# Audio_interface.net
KiCad netlist of a schematic drawn in EAGLE
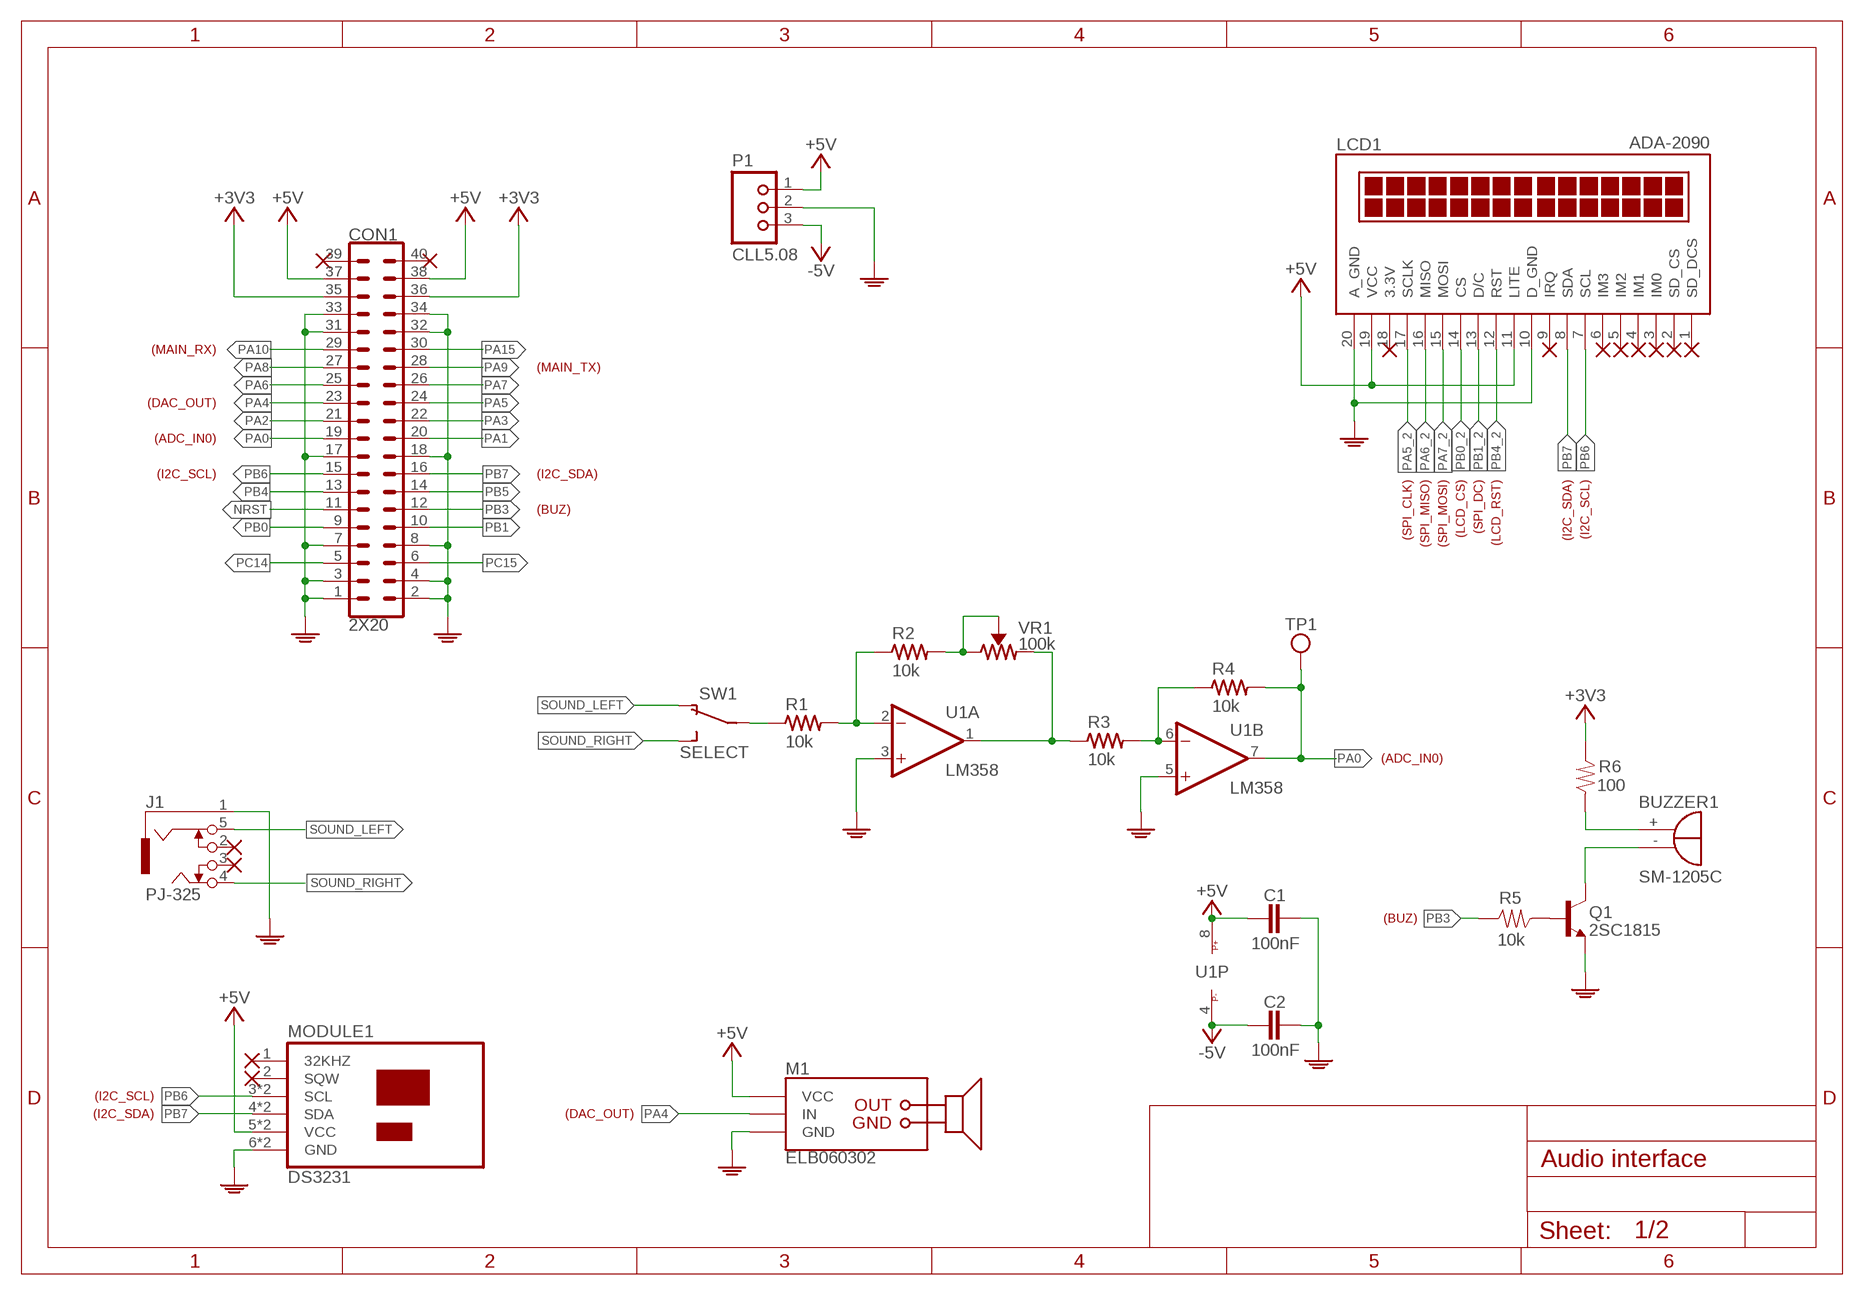
[diagram p0: schematic, sheet 1]
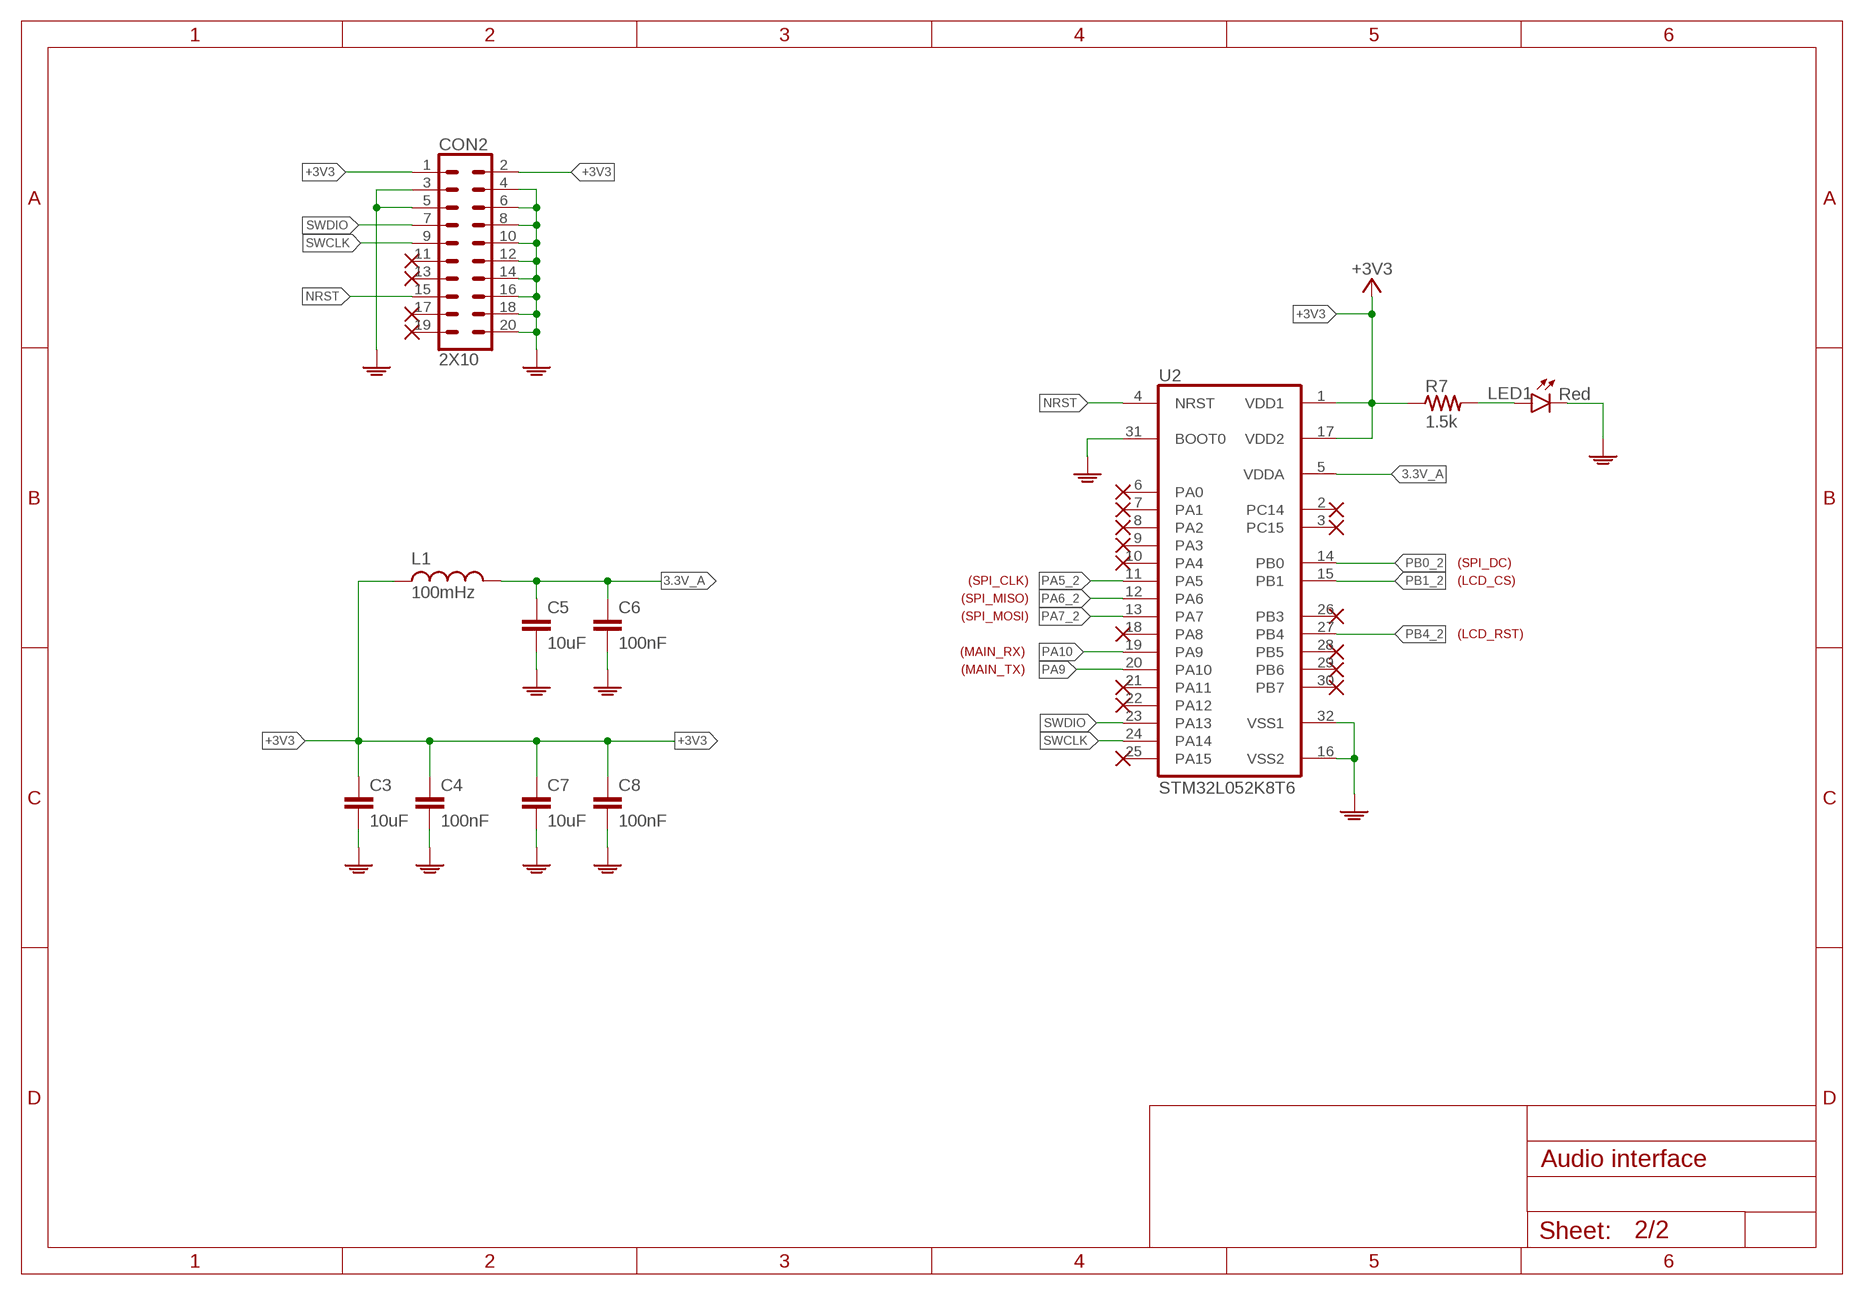
[diagram p1: schematic, sheet 2]

(export (version "E")
  (design (tool "Eeschema 10.0.6"))
  (components
    (comp (ref "C3")
      (value "10uF")
      (footprint "eagle-import:C0603K")
      (libsource (lib "eagle-import") (part "C-EUC0603K"))
    )
    (comp (ref "C4")
      (value "100nF")
      (footprint "eagle-import:C2012")
      (libsource (lib "eagle-import") (part "C-EUC2012"))
    )
    (comp (ref "C5")
      (value "10uF")
      (footprint "eagle-import:C0603K")
      (libsource (lib "eagle-import") (part "C-EUC0603K"))
    )
    (comp (ref "C6")
      (value "100nF")
      (footprint "eagle-import:C2012")
      (libsource (lib "eagle-import") (part "C-EUC2012"))
    )
    (comp (ref "C7")
      (value "10uF")
      (footprint "eagle-import:C0603K")
      (libsource (lib "eagle-import") (part "C-EUC0603K"))
    )
    (comp (ref "C8")
      (value "100nF")
      (footprint "eagle-import:C2012")
      (libsource (lib "eagle-import") (part "C-EUC2012"))
    )
    (comp (ref "CON2")
      (value "2X10")
      (footprint "eagle-import:2X10(MALE)")
      (libsource (lib "eagle-import") (part "HEADER_2X10_(PIN)"))
    )
    (comp (ref "L1")
      (value "100mHz")
      (footprint "eagle-import:C0603K")
      (libsource (lib "eagle-import") (part "L-US"))
    )
    (comp (ref "LED1")
      (value "Red")
      (footprint "eagle-import:CHIP_0805(LED)")
      (libsource (lib "eagle-import") (part "LED(1-COLOR)_(0805)"))
    )
    (comp (ref "R7")
      (value "1.5k")
      (footprint "eagle-import:2012")
      (libsource (lib "eagle-import") (part "RES_(2012)"))
    )
    (comp (ref "U2")
      (value "STM32L052K8T6")
      (footprint "eagle-import:LQFP32")
      (libsource (lib "eagle-import") (part "STM32L052K6T6"))
    )
    (comp (ref "BUZZER1")
      (value "SM-1205C")
      (footprint "eagle-import:SM-1205C")
      (libsource (lib "eagle-import") (part "BUZZER_(SM-1205C)"))
    )
    (comp (ref "C1")
      (value "100nF")
      (footprint "eagle-import:C2012")
      (libsource (lib "eagle-import") (part "C-EUC2012"))
    )
    (comp (ref "C2")
      (value "100nF")
      (footprint "eagle-import:C2012")
      (libsource (lib "eagle-import") (part "C-EUC2012"))
    )
    (comp (ref "CON1")
      (value "2X20")
      (footprint "eagle-import:2X20_VER3DEFORMATION")
      (libsource (lib "eagle-import") (part "HEADER_2X20_(VER_3DEFORMATION)"))
    )
    (comp (ref "J1")
      (value "PJ-325")
      (footprint "eagle-import:PJ-325")
      (libsource (lib "eagle-import") (part "JACK(STEREO)_(PJ-325)"))
    )
    (comp (ref "LCD1")
      (value "ADA-2090")
      (footprint "eagle-import:TOUCH_SCREEN")
      (libsource (lib "eagle-import") (part "MODULE(ADA-1770)"))
    )
    (comp (ref "M1")
      (value "ELB060302")
      (footprint "eagle-import:MODULE(ELB060302)")
      (libsource (lib "eagle-import") (part "MODULE(ELB060302)"))
    )
    (comp (ref "MODULE1")
      (value "DS3231")
      (footprint "eagle-import:MODULE(DS3231)")
      (libsource (lib "eagle-import") (part "MODULE(DS3231)"))
    )
    (comp (ref "P1")
      (value "CLL5.08")
      (footprint "eagle-import:TERMINAL(CLL5.08-03P)")
      (libsource (lib "eagle-import") (part "TERMINAL(3P)_(CLL5.08)"))
    )
    (comp (ref "Q1")
      (value "2SC1815")
      (footprint "eagle-import:SOT23")
      (libsource (lib "eagle-import") (part "TR_BJT(NPN)_(SOT23)"))
    )
    (comp (ref "R1")
      (value "10k")
      (footprint "eagle-import:2012")
      (libsource (lib "eagle-import") (part "RES_(2012)"))
    )
    (comp (ref "R2")
      (value "10k")
      (footprint "eagle-import:2012")
      (libsource (lib "eagle-import") (part "RES_(2012)"))
    )
    (comp (ref "R3")
      (value "10k")
      (footprint "eagle-import:2012")
      (libsource (lib "eagle-import") (part "RES_(2012)"))
    )
    (comp (ref "R4")
      (value "10k")
      (footprint "eagle-import:2012")
      (libsource (lib "eagle-import") (part "RES_(2012)"))
    )
    (comp (ref "R5")
      (value "10k")
      (footprint "eagle-import:2012")
      (libsource (lib "eagle-import") (part "RESSMD"))
    )
    (comp (ref "R6")
      (value "100")
      (footprint "eagle-import:2012")
      (libsource (lib "eagle-import") (part "RESSMD"))
    )
    (comp (ref "SW1")
      (value "SELECT")
      (footprint "eagle-import:SW(MSL-1C2P)")
      (libsource (lib "eagle-import") (part "SW(SPDT)_(MSL-1C2P)"))
    )
    (comp (ref "TP1")
      (value "TP_(LC-2-G)")
      (footprint "eagle-import:TP(LC-2-G)")
      (libsource (lib "eagle-import") (part "TP_(LC-2-G)"))
    )
    (comp (ref "U1")
      (value "LM358")
      (footprint "eagle-import:SO8(150MIL)")
      (libsource (lib "eagle-import") (part "LM358_(SO)"))
    )
    (comp (ref "VR1")
      (value "100k")
      (footprint "eagle-import:RTRIM(VZ067TL7)")
      (libsource (lib "eagle-import") (part "RES(VARIABLE)_(VZ067TL7)"))
    )
  )
  (nets
    (net (code "1") (name "+3V3") (class "Default")
      (node (ref "C3") (pin "1") (pinfunction "1_1") (pintype "passive"))
      (node (ref "C4") (pin "1") (pinfunction "1_1") (pintype "passive"))
      (node (ref "C7") (pin "1") (pinfunction "1_1") (pintype "passive"))
      (node (ref "C8") (pin "1") (pinfunction "1_1") (pintype "passive"))
      (node (ref "CON1") (pin "35") (pinfunction "35_35") (pintype "passive"))
      (node (ref "CON1") (pin "36") (pinfunction "36_36") (pintype "passive"))
      (node (ref "CON2") (pin "1") (pinfunction "1_1") (pintype "passive"))
      (node (ref "CON2") (pin "2") (pinfunction "2_2") (pintype "passive"))
      (node (ref "L1") (pin "1") (pinfunction "1_1") (pintype "passive"))
      (node (ref "R6") (pin "2") (pinfunction "2_2") (pintype "bidirectional"))
      (node (ref "R7") (pin "1") (pinfunction "1_1") (pintype "passive"))
      (node (ref "U2") (pin "1") (pinfunction "VDD1_1") (pintype "power_in"))
      (node (ref "U2") (pin "17") (pinfunction "VDD2_17") (pintype "power_in"))
    )
    (net (code "2") (name "+5V") (class "Default")
      (node (ref "C1") (pin "1") (pinfunction "1_1") (pintype "passive"))
      (node (ref "CON1") (pin "37") (pinfunction "37_37") (pintype "passive"))
      (node (ref "CON1") (pin "38") (pinfunction "38_38") (pintype "passive"))
      (node (ref "LCD1") (pin "11") (pinfunction "LITE_11") (pintype "bidirectional"))
      (node (ref "LCD1") (pin "19") (pinfunction "VCC_19") (pintype "bidirectional"))
      (node (ref "M1") (pin "2") (pinfunction "VCC_2") (pintype "bidirectional"))
      (node (ref "MODULE1") (pin "5") (pinfunction "VCC_5") (pintype "power_in"))
      (node (ref "MODULE1") (pin "9") (pinfunction "VCC_9") (pintype "power_in"))
      (node (ref "P1") (pin "1") (pinfunction "1_1") (pintype "passive"))
      (node (ref "U1") (pin "8") (pinfunction "P+_8") (pintype "power_in"))
    )
    (net (code "3") (name "-5V") (class "Default")
      (node (ref "C2") (pin "1") (pinfunction "1_1") (pintype "passive"))
      (node (ref "P1") (pin "3") (pinfunction "3_3") (pintype "passive"))
      (node (ref "U1") (pin "4") (pinfunction "P-_4") (pintype "power_in"))
    )
    (net (code "4") (name "3.3V_A") (class "Default")
      (node (ref "C5") (pin "1") (pinfunction "1_1") (pintype "passive"))
      (node (ref "C6") (pin "1") (pinfunction "1_1") (pintype "passive"))
      (node (ref "L1") (pin "2") (pinfunction "2_2") (pintype "passive"))
      (node (ref "U2") (pin "5") (pinfunction "VDDA_5") (pintype "power_in"))
    )
    (net (code "5") (name "GND") (class "Default")
      (node (ref "C1") (pin "2") (pinfunction "2_2") (pintype "passive"))
      (node (ref "C2") (pin "2") (pinfunction "2_2") (pintype "passive"))
      (node (ref "C3") (pin "2") (pinfunction "2_2") (pintype "passive"))
      (node (ref "C4") (pin "2") (pinfunction "2_2") (pintype "passive"))
      (node (ref "C5") (pin "2") (pinfunction "2_2") (pintype "passive"))
      (node (ref "C6") (pin "2") (pinfunction "2_2") (pintype "passive"))
      (node (ref "C7") (pin "2") (pinfunction "2_2") (pintype "passive"))
      (node (ref "C8") (pin "2") (pinfunction "2_2") (pintype "passive"))
      (node (ref "CON1") (pin "1") (pinfunction "1_1") (pintype "passive"))
      (node (ref "CON1") (pin "17") (pinfunction "17_17") (pintype "passive"))
      (node (ref "CON1") (pin "18") (pinfunction "18_18") (pintype "passive"))
      (node (ref "CON1") (pin "2") (pinfunction "2_2") (pintype "passive"))
      (node (ref "CON1") (pin "3") (pinfunction "3_3") (pintype "passive"))
      (node (ref "CON1") (pin "31") (pinfunction "31_31") (pintype "passive"))
      (node (ref "CON1") (pin "32") (pinfunction "32_32") (pintype "passive"))
      (node (ref "CON1") (pin "33") (pinfunction "33_33") (pintype "passive"))
      (node (ref "CON1") (pin "34") (pinfunction "34_34") (pintype "passive"))
      (node (ref "CON1") (pin "4") (pinfunction "4_4") (pintype "passive"))
      (node (ref "CON1") (pin "7") (pinfunction "7_7") (pintype "passive"))
      (node (ref "CON1") (pin "8") (pinfunction "8_8") (pintype "passive"))
      (node (ref "CON2") (pin "10") (pinfunction "10_10") (pintype "passive"))
      (node (ref "CON2") (pin "12") (pinfunction "12_12") (pintype "passive"))
      (node (ref "CON2") (pin "14") (pinfunction "14_14") (pintype "passive"))
      (node (ref "CON2") (pin "16") (pinfunction "16_16") (pintype "passive"))
      (node (ref "CON2") (pin "18") (pinfunction "18_18") (pintype "passive"))
      (node (ref "CON2") (pin "20") (pinfunction "20_20") (pintype "passive"))
      (node (ref "CON2") (pin "3") (pinfunction "3_3") (pintype "passive"))
      (node (ref "CON2") (pin "4") (pinfunction "4_4") (pintype "passive"))
      (node (ref "CON2") (pin "5") (pinfunction "5_5") (pintype "passive"))
      (node (ref "CON2") (pin "6") (pinfunction "6_6") (pintype "passive"))
      (node (ref "CON2") (pin "8") (pinfunction "8_8") (pintype "passive"))
      (node (ref "J1") (pin "1") (pinfunction "GND_1") (pintype "passive"))
      (node (ref "LCD1") (pin "10") (pinfunction "D_GND_10") (pintype "bidirectional"))
      (node (ref "LCD1") (pin "20") (pinfunction "A_GND_20") (pintype "bidirectional"))
      (node (ref "LED1") (pin "1") (pinfunction "C_1") (pintype "passive"))
      (node (ref "M1") (pin "3") (pinfunction "GND_3") (pintype "bidirectional"))
      (node (ref "MODULE1") (pin "10") (pinfunction "GND_10") (pintype "power_in"))
      (node (ref "MODULE1") (pin "6") (pinfunction "GND_6") (pintype "power_in"))
      (node (ref "P1") (pin "2") (pinfunction "2_2") (pintype "passive"))
      (node (ref "Q1") (pin "2") (pinfunction "E_2") (pintype "passive"))
      (node (ref "U1") (pin "3") (pinfunction "+IN_3") (pintype "input"))
      (node (ref "U1") (pin "5") (pinfunction "+IN_5") (pintype "input"))
      (node (ref "U2") (pin "16") (pinfunction "VSS2_16") (pintype "power_in"))
      (node (ref "U2") (pin "31") (pinfunction "BOOT0_31") (pintype "input"))
      (node (ref "U2") (pin "32") (pinfunction "VSS1_32") (pintype "power_in"))
    )
    (net (code "6") (name "NRST") (class "Default")
      (node (ref "CON1") (pin "11") (pinfunction "11_11") (pintype "passive"))
      (node (ref "CON2") (pin "15") (pinfunction "15_15") (pintype "passive"))
      (node (ref "U2") (pin "4") (pinfunction "NRST_4") (pintype "input"))
    )
    (net (code "7") (name "Net-(BUZZER1-Pad+)") (class "Default")
      (node (ref "BUZZER1") (pin "+") (pinfunction "+_+") (pintype "passive"))
      (node (ref "R6") (pin "1") (pinfunction "1_1") (pintype "bidirectional"))
    )
    (net (code "8") (name "Net-(LED1-A)") (class "Default")
      (node (ref "LED1") (pin "2") (pinfunction "A_2") (pintype "passive"))
      (node (ref "R7") (pin "2") (pinfunction "2_2") (pintype "passive"))
    )
    (net (code "9") (name "Net-(Q1-B)") (class "Default")
      (node (ref "Q1") (pin "1") (pinfunction "B_1") (pintype "passive"))
      (node (ref "R5") (pin "1") (pinfunction "1_1") (pintype "bidirectional"))
    )
    (net (code "10") (name "Net-(Q1-C)") (class "Default")
      (node (ref "BUZZER1") (pin "-") (pinfunction "-_-") (pintype "passive"))
      (node (ref "Q1") (pin "3") (pinfunction "C_3") (pintype "passive"))
    )
    (net (code "11") (name "Net-(SW1-P)") (class "Default")
      (node (ref "R1") (pin "1") (pinfunction "1_1") (pintype "passive"))
      (node (ref "SW1") (pin "2") (pinfunction "P_2") (pintype "passive"))
    )
    (net (code "12") (name "Net-(U1A--IN)") (class "Default")
      (node (ref "R1") (pin "2") (pinfunction "2_2") (pintype "passive"))
      (node (ref "R2") (pin "1") (pinfunction "1_1") (pintype "passive"))
      (node (ref "U1") (pin "2") (pinfunction "-IN_2") (pintype "input"))
    )
    (net (code "13") (name "Net-(U1A-OUT)") (class "Default")
      (node (ref "R3") (pin "1") (pinfunction "1_1") (pintype "passive"))
      (node (ref "U1") (pin "1") (pinfunction "OUT_1") (pintype "output"))
      (node (ref "VR1") (pin "BOT") (pinfunction "CCW_BOT") (pintype "passive"))
    )
    (net (code "14") (name "Net-(U1B--IN)") (class "Default")
      (node (ref "R3") (pin "2") (pinfunction "2_2") (pintype "passive"))
      (node (ref "R4") (pin "1") (pinfunction "1_1") (pintype "passive"))
      (node (ref "U1") (pin "6") (pinfunction "-IN_6") (pintype "input"))
    )
    (net (code "15") (name "Net-(VR1-CW)") (class "Default")
      (node (ref "R2") (pin "2") (pinfunction "2_2") (pintype "passive"))
      (node (ref "VR1") (pin "TAP") (pinfunction "WIPER_TAP") (pintype "passive"))
      (node (ref "VR1") (pin "TOP") (pinfunction "CW_TOP") (pintype "passive"))
    )
    (net (code "16") (name "PA0") (class "Default")
      (node (ref "CON1") (pin "19") (pinfunction "19_19") (pintype "passive"))
      (node (ref "R4") (pin "2") (pinfunction "2_2") (pintype "passive"))
      (node (ref "TP1") (pin "1") (pinfunction "P$1_1") (pintype "passive"))
      (node (ref "U1") (pin "7") (pinfunction "OUT_7") (pintype "output"))
    )
    (net (code "17") (name "PA1") (class "Default")
      (node (ref "CON1") (pin "20") (pinfunction "20_20") (pintype "passive"))
    )
    (net (code "18") (name "PA2") (class "Default")
      (node (ref "CON1") (pin "21") (pinfunction "21_21") (pintype "passive"))
    )
    (net (code "19") (name "PA3") (class "Default")
      (node (ref "CON1") (pin "22") (pinfunction "22_22") (pintype "passive"))
    )
    (net (code "20") (name "PA4") (class "Default")
      (node (ref "CON1") (pin "23") (pinfunction "23_23") (pintype "passive"))
      (node (ref "M1") (pin "1") (pinfunction "IN_1") (pintype "bidirectional"))
    )
    (net (code "21") (name "PA5") (class "Default")
      (node (ref "CON1") (pin "24") (pinfunction "24_24") (pintype "passive"))
    )
    (net (code "22") (name "PA5_2") (class "Default")
      (node (ref "LCD1") (pin "17") (pinfunction "SCLK_17") (pintype "bidirectional"))
      (node (ref "U2") (pin "11") (pinfunction "PA5_11") (pintype "bidirectional"))
    )
    (net (code "23") (name "PA6") (class "Default")
      (node (ref "CON1") (pin "25") (pinfunction "25_25") (pintype "passive"))
    )
    (net (code "24") (name "PA6_2") (class "Default")
      (node (ref "LCD1") (pin "16") (pinfunction "MISO_16") (pintype "bidirectional"))
      (node (ref "U2") (pin "12") (pinfunction "PA6_12") (pintype "bidirectional"))
    )
    (net (code "25") (name "PA7") (class "Default")
      (node (ref "CON1") (pin "26") (pinfunction "26_26") (pintype "passive"))
    )
    (net (code "26") (name "PA7_2") (class "Default")
      (node (ref "LCD1") (pin "15") (pinfunction "MOSI_15") (pintype "bidirectional"))
      (node (ref "U2") (pin "13") (pinfunction "PA7_13") (pintype "bidirectional"))
    )
    (net (code "27") (name "PA8") (class "Default")
      (node (ref "CON1") (pin "27") (pinfunction "27_27") (pintype "passive"))
    )
    (net (code "28") (name "PA9") (class "Default")
      (node (ref "CON1") (pin "28") (pinfunction "28_28") (pintype "passive"))
      (node (ref "U2") (pin "20") (pinfunction "PA10_20") (pintype "bidirectional"))
    )
    (net (code "29") (name "PA10") (class "Default")
      (node (ref "CON1") (pin "29") (pinfunction "29_29") (pintype "passive"))
      (node (ref "U2") (pin "19") (pinfunction "PA9_19") (pintype "bidirectional"))
    )
    (net (code "30") (name "PA15") (class "Default")
      (node (ref "CON1") (pin "30") (pinfunction "30_30") (pintype "passive"))
    )
    (net (code "31") (name "PB0") (class "Default")
      (node (ref "CON1") (pin "9") (pinfunction "9_9") (pintype "passive"))
    )
    (net (code "32") (name "PB0_2") (class "Default")
      (node (ref "LCD1") (pin "14") (pinfunction "CS_14") (pintype "bidirectional"))
      (node (ref "U2") (pin "14") (pinfunction "PB0_14") (pintype "bidirectional"))
    )
    (net (code "33") (name "PB1") (class "Default")
      (node (ref "CON1") (pin "10") (pinfunction "10_10") (pintype "passive"))
    )
    (net (code "34") (name "PB1_2") (class "Default")
      (node (ref "LCD1") (pin "13") (pinfunction "D/C_13") (pintype "bidirectional"))
      (node (ref "U2") (pin "15") (pinfunction "PB1_15") (pintype "bidirectional"))
    )
    (net (code "35") (name "PB3") (class "Default")
      (node (ref "CON1") (pin "12") (pinfunction "12_12") (pintype "passive"))
      (node (ref "R5") (pin "2") (pinfunction "2_2") (pintype "bidirectional"))
    )
    (net (code "36") (name "PB4") (class "Default")
      (node (ref "CON1") (pin "13") (pinfunction "13_13") (pintype "passive"))
    )
    (net (code "37") (name "PB4_2") (class "Default")
      (node (ref "LCD1") (pin "12") (pinfunction "RST_12") (pintype "bidirectional"))
      (node (ref "U2") (pin "27") (pinfunction "PB4_27") (pintype "bidirectional"))
    )
    (net (code "38") (name "PB5") (class "Default")
      (node (ref "CON1") (pin "14") (pinfunction "14_14") (pintype "passive"))
    )
    (net (code "39") (name "PB6") (class "Default")
      (node (ref "CON1") (pin "15") (pinfunction "15_15") (pintype "passive"))
      (node (ref "LCD1") (pin "7") (pinfunction "SCL_7") (pintype "bidirectional"))
      (node (ref "MODULE1") (pin "3") (pinfunction "SCL_3") (pintype "input"))
      (node (ref "MODULE1") (pin "7") (pinfunction "SCL_7") (pintype "input"))
    )
    (net (code "40") (name "PB7") (class "Default")
      (node (ref "CON1") (pin "16") (pinfunction "16_16") (pintype "passive"))
      (node (ref "LCD1") (pin "8") (pinfunction "SDA_8") (pintype "bidirectional"))
      (node (ref "MODULE1") (pin "4") (pinfunction "SDA_4") (pintype "bidirectional"))
      (node (ref "MODULE1") (pin "8") (pinfunction "SDA_8") (pintype "bidirectional"))
    )
    (net (code "41") (name "PC14") (class "Default")
      (node (ref "CON1") (pin "5") (pinfunction "5_5") (pintype "passive"))
    )
    (net (code "42") (name "PC15") (class "Default")
      (node (ref "CON1") (pin "6") (pinfunction "6_6") (pintype "passive"))
    )
    (net (code "43") (name "SOUND_LEFT") (class "Default")
      (node (ref "J1") (pin "5") (pinfunction "SP1_5") (pintype "passive"))
      (node (ref "SW1") (pin "1") (pinfunction "O_1") (pintype "passive"))
    )
    (net (code "44") (name "SOUND_RIGHT") (class "Default")
      (node (ref "J1") (pin "4") (pinfunction "SP2_4") (pintype "passive"))
      (node (ref "SW1") (pin "3") (pinfunction "S_3") (pintype "passive"))
    )
    (net (code "45") (name "SWCLK") (class "Default")
      (node (ref "CON2") (pin "9") (pinfunction "9_9") (pintype "passive"))
      (node (ref "U2") (pin "24") (pinfunction "PA14_24") (pintype "bidirectional"))
    )
    (net (code "46") (name "SWDIO") (class "Default")
      (node (ref "CON2") (pin "7") (pinfunction "7_7") (pintype "passive"))
      (node (ref "U2") (pin "23") (pinfunction "PA13_23") (pintype "bidirectional"))
    )
    (net (code "47") (name "unconnected-(CON1-Pad39)") (class "Default")
      (node (ref "CON1") (pin "39") (pinfunction "39_39") (pintype "passive"))
    )
    (net (code "48") (name "unconnected-(CON1-Pad40)") (class "Default")
      (node (ref "CON1") (pin "40") (pinfunction "40_40") (pintype "passive"))
    )
    (net (code "49") (name "unconnected-(CON2-Pad11)") (class "Default")
      (node (ref "CON2") (pin "11") (pinfunction "11_11") (pintype "passive"))
    )
    (net (code "50") (name "unconnected-(CON2-Pad13)") (class "Default")
      (node (ref "CON2") (pin "13") (pinfunction "13_13") (pintype "passive"))
    )
    (net (code "51") (name "unconnected-(CON2-Pad17)") (class "Default")
      (node (ref "CON2") (pin "17") (pinfunction "17_17") (pintype "passive"))
    )
    (net (code "52") (name "unconnected-(CON2-Pad19)") (class "Default")
      (node (ref "CON2") (pin "19") (pinfunction "19_19") (pintype "passive"))
    )
    (net (code "53") (name "unconnected-(J1-CP1-Pad2)") (class "Default")
      (node (ref "J1") (pin "2") (pinfunction "CP1_2") (pintype "passive"))
    )
    (net (code "54") (name "unconnected-(J1-CP2-Pad3)") (class "Default")
      (node (ref "J1") (pin "3") (pinfunction "CP2_3") (pintype "passive"))
    )
    (net (code "55") (name "unconnected-(LCD1-3.3V-Pad18)") (class "Default")
      (node (ref "LCD1") (pin "18") (pinfunction "3.3V_18") (pintype "bidirectional"))
    )
    (net (code "56") (name "unconnected-(LCD1-IM0-Pad3)") (class "Default")
      (node (ref "LCD1") (pin "3") (pinfunction "IM0_3") (pintype "bidirectional"))
    )
    (net (code "57") (name "unconnected-(LCD1-IM1-Pad4)") (class "Default")
      (node (ref "LCD1") (pin "4") (pinfunction "IM1_4") (pintype "bidirectional"))
    )
    (net (code "58") (name "unconnected-(LCD1-IM2-Pad5)") (class "Default")
      (node (ref "LCD1") (pin "5") (pinfunction "IM2_5") (pintype "bidirectional"))
    )
    (net (code "59") (name "unconnected-(LCD1-IM3-Pad6)") (class "Default")
      (node (ref "LCD1") (pin "6") (pinfunction "IM3_6") (pintype "bidirectional"))
    )
    (net (code "60") (name "unconnected-(LCD1-IRQ-Pad9)") (class "Default")
      (node (ref "LCD1") (pin "9") (pinfunction "IRQ_9") (pintype "bidirectional"))
    )
    (net (code "61") (name "unconnected-(LCD1-SD_CS-Pad2)") (class "Default")
      (node (ref "LCD1") (pin "2") (pinfunction "SD_CS_2") (pintype "bidirectional"))
    )
    (net (code "62") (name "unconnected-(LCD1-SD_DCS-Pad1)") (class "Default")
      (node (ref "LCD1") (pin "1") (pinfunction "SD_DCS_1") (pintype "bidirectional"))
    )
    (net (code "63") (name "unconnected-(MODULE1-32KHZ-Pad1)") (class "Default")
      (node (ref "MODULE1") (pin "1") (pinfunction "32KHZ_1") (pintype "output"))
    )
    (net (code "64") (name "unconnected-(MODULE1-SQW-Pad2)") (class "Default")
      (node (ref "MODULE1") (pin "2") (pinfunction "SQW_2") (pintype "output"))
    )
    (net (code "65") (name "unconnected-(U2-PA0-Pad6)") (class "Default")
      (node (ref "U2") (pin "6") (pinfunction "PA0_6") (pintype "bidirectional"))
    )
    (net (code "66") (name "unconnected-(U2-PA1-Pad7)") (class "Default")
      (node (ref "U2") (pin "7") (pinfunction "PA1_7") (pintype "bidirectional"))
    )
    (net (code "67") (name "unconnected-(U2-PA2-Pad8)") (class "Default")
      (node (ref "U2") (pin "8") (pinfunction "PA2_8") (pintype "bidirectional"))
    )
    (net (code "68") (name "unconnected-(U2-PA3-Pad9)") (class "Default")
      (node (ref "U2") (pin "9") (pinfunction "PA3_9") (pintype "bidirectional"))
    )
    (net (code "69") (name "unconnected-(U2-PA4-Pad10)") (class "Default")
      (node (ref "U2") (pin "10") (pinfunction "PA4_10") (pintype "bidirectional"))
    )
    (net (code "70") (name "unconnected-(U2-PA8-Pad18)") (class "Default")
      (node (ref "U2") (pin "18") (pinfunction "PA8_18") (pintype "bidirectional"))
    )
    (net (code "71") (name "unconnected-(U2-PA11-Pad21)") (class "Default")
      (node (ref "U2") (pin "21") (pinfunction "PA11_21") (pintype "bidirectional"))
    )
    (net (code "72") (name "unconnected-(U2-PA12-Pad22)") (class "Default")
      (node (ref "U2") (pin "22") (pinfunction "PA12_22") (pintype "bidirectional"))
    )
    (net (code "73") (name "unconnected-(U2-PA15-Pad25)") (class "Default")
      (node (ref "U2") (pin "25") (pinfunction "PA15_25") (pintype "bidirectional"))
    )
    (net (code "74") (name "unconnected-(U2-PB3-Pad26)") (class "Default")
      (node (ref "U2") (pin "26") (pinfunction "PB3_26") (pintype "bidirectional"))
    )
    (net (code "75") (name "unconnected-(U2-PB5-Pad28)") (class "Default")
      (node (ref "U2") (pin "28") (pinfunction "PB5_28") (pintype "bidirectional"))
    )
    (net (code "76") (name "unconnected-(U2-PB6-Pad29)") (class "Default")
      (node (ref "U2") (pin "29") (pinfunction "PB6_29") (pintype "bidirectional"))
    )
    (net (code "77") (name "unconnected-(U2-PB7-Pad30)") (class "Default")
      (node (ref "U2") (pin "30") (pinfunction "PB7_30") (pintype "bidirectional"))
    )
    (net (code "78") (name "unconnected-(U2-PC14-Pad2)") (class "Default")
      (node (ref "U2") (pin "2") (pinfunction "PC14_2") (pintype "bidirectional"))
    )
    (net (code "79") (name "unconnected-(U2-PC15-Pad3)") (class "Default")
      (node (ref "U2") (pin "3") (pinfunction "PC15_3") (pintype "bidirectional"))
    )
  )
)
